# DCDC_int.net
KiCad netlist of a schematic drawn in Altium Designer
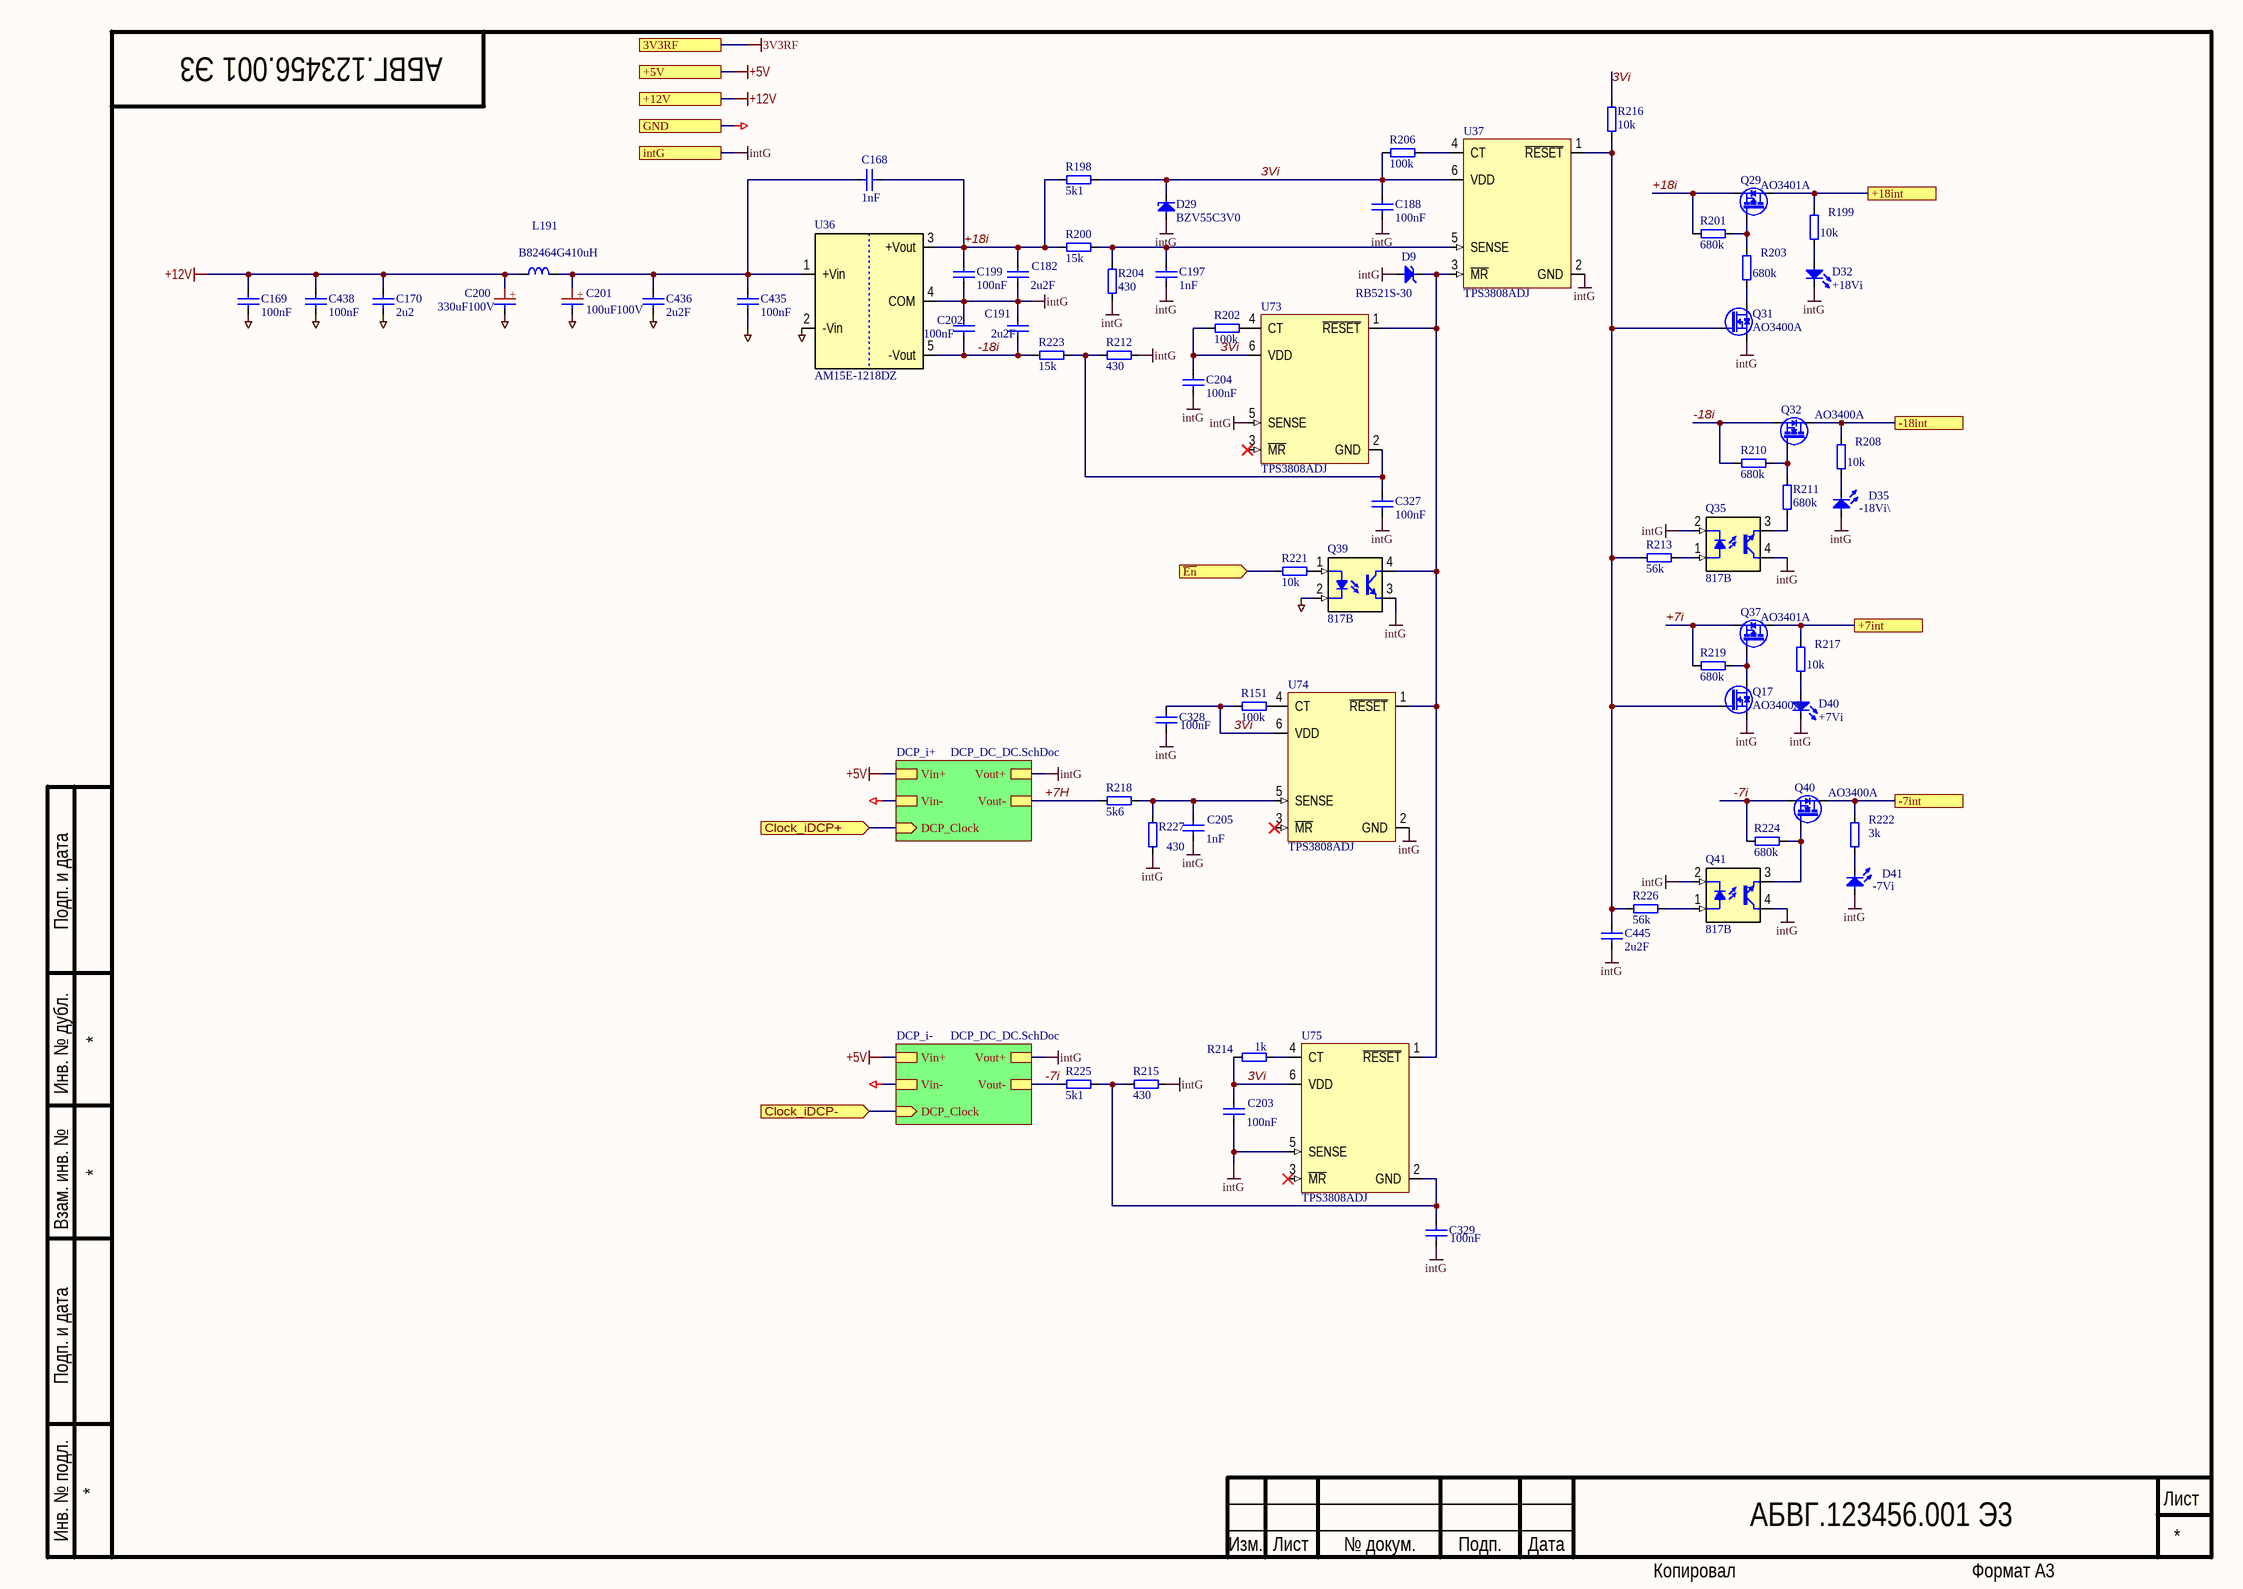
[diagram p0: DCDC_int.SchDoc]

(export (version "E")
  (design (tool "Eeschema 10.0.6"))
  (components
    (comp (ref "C168")
      (value "1nF")
      (footprint "SMD0805CAP")
      (description "Чип конденсатор 0805")
      (fields (field (name "VOLTAGE") "25V") (field (name "TOLERANCE") "20%"))
      (libsource (lib "DDSintLib") (part "C0805"))
    )
    (comp (ref "C169")
      (value "100nF")
      (footprint "SMD0805CAP")
      (description "Чип конденсатор 0805")
      (fields (field (name "VOLTAGE") "25V") (field (name "TOLERANCE") "20%"))
      (libsource (lib "DDSintLib") (part "C0805"))
    )
    (comp (ref "C170")
      (value "2u2")
      (footprint "SMD0805CAP")
      (description "Чип конденсатор 0805")
      (fields (field (name "VOLTAGE") "25V") (field (name "TOLERANCE") "20%"))
      (libsource (lib "DDSintLib") (part "C0805"))
    )
    (comp (ref "C182")
      (value "2u2F")
      (footprint "SMD0805CAP")
      (description "Чип конденсатор 0805")
      (fields (field (name "VOLTAGE") "25V") (field (name "TOLERANCE") "20%"))
      (libsource (lib "DDSintLib") (part "C0805"))
    )
    (comp (ref "C188")
      (value "100nF")
      (footprint "SMD0805CAP")
      (description "Чип конденсатор 0805")
      (fields (field (name "VOLTAGE") "25V") (field (name "TOLERANCE") "20%"))
      (libsource (lib "DDSintLib") (part "C0805"))
    )
    (comp (ref "C191")
      (value "2u2F")
      (footprint "SMD0805CAP")
      (description "Чип конденсатор 0805")
      (fields (field (name "VOLTAGE") "25V") (field (name "TOLERANCE") "20%"))
      (libsource (lib "DDSintLib") (part "C0805"))
    )
    (comp (ref "C197")
      (value "1nF")
      (footprint "SMD0805CAP")
      (description "Чип конденсатор 0805")
      (fields (field (name "VOLTAGE") "25V") (field (name "TOLERANCE") "20%"))
      (libsource (lib "DDSintLib") (part "C0805"))
    )
    (comp (ref "C199")
      (value "100nF")
      (footprint "SMD0805CAP")
      (description "Чип конденсатор 0805")
      (fields (field (name "VOLTAGE") "25V") (field (name "TOLERANCE") "20%"))
      (libsource (lib "DDSintLib") (part "C0805"))
    )
    (comp (ref "C200")
      (value "330uF100V")
      (footprint "CAPPR750-1600X2000")
      (description "Конденсатор полярный d16 p7.5мм")
      (fields (field (name "VOLTAGE") "100V") (field (name "TOLERANCE") "20%"))
      (libsource (lib "DDSintLib") (part "CAP_POL_7_5x16"))
    )
    (comp (ref "C201")
      (value "100uF100V")
      (footprint "CAPPR500-1000X1250")
      (description "Конденсатор полярный d10 p5мм")
      (fields (field (name "VOLTAGE") "100V") (field (name "TOLERANCE") "20%"))
      (libsource (lib "DDS1") (part "CAP_POL_5x10"))
    )
    (comp (ref "C202")
      (value "100nF")
      (footprint "SMD0805CAP")
      (description "Чип конденсатор 0805")
      (fields (field (name "VOLTAGE") "25V") (field (name "TOLERANCE") "20%"))
      (libsource (lib "DDSintLib") (part "C0805"))
    )
    (comp (ref "C203")
      (value "100nF")
      (footprint "SMD0805CAP")
      (description "Чип конденсатор 0805")
      (fields (field (name "VOLTAGE") "25V") (field (name "TOLERANCE") "20%"))
      (libsource (lib "DDSintLib") (part "C0805"))
    )
    (comp (ref "C204")
      (value "100nF")
      (footprint "SMD0805CAP")
      (description "Чип конденсатор 0805")
      (fields (field (name "VOLTAGE") "25V") (field (name "TOLERANCE") "20%"))
      (libsource (lib "DDSintLib") (part "C0805"))
    )
    (comp (ref "C205")
      (value "1nF")
      (footprint "SMD0805CAP")
      (description "Чип конденсатор 0805")
      (fields (field (name "VOLTAGE") "25V") (field (name "TOLERANCE") "20%"))
      (libsource (lib "DDSintLib") (part "C0805"))
    )
    (comp (ref "C327")
      (value "100nF")
      (footprint "SMD0805CAP")
      (description "Чип конденсатор 0805")
      (fields (field (name "VOLTAGE") "25V") (field (name "TOLERANCE") "20%"))
      (libsource (lib "DDSintLib") (part "C0805"))
    )
    (comp (ref "C328")
      (value "100nF")
      (footprint "SMD0805CAP")
      (description "Чип конденсатор 0805")
      (fields (field (name "VOLTAGE") "25V") (field (name "TOLERANCE") "20%"))
      (libsource (lib "DDSintLib") (part "C0805"))
    )
    (comp (ref "C329")
      (value "100nF")
      (footprint "SMD0805CAP")
      (description "Чип конденсатор 0805")
      (fields (field (name "VOLTAGE") "25V") (field (name "TOLERANCE") "20%"))
      (libsource (lib "DDSintLib") (part "C0805"))
    )
    (comp (ref "C435")
      (value "100nF")
      (footprint "SMD0805CAP")
      (description "Чип конденсатор 0805")
      (fields (field (name "VOLTAGE") "25V") (field (name "TOLERANCE") "20%"))
      (libsource (lib "DDSintLib") (part "C0805"))
    )
    (comp (ref "C436")
      (value "2u2F")
      (footprint "SMD0805CAP")
      (description "Чип конденсатор 0805")
      (fields (field (name "VOLTAGE") "25V") (field (name "TOLERANCE") "20%"))
      (libsource (lib "DDSintLib") (part "C0805"))
    )
    (comp (ref "C438")
      (value "100nF")
      (footprint "SMD0805CAP")
      (description "Чип конденсатор 0805")
      (fields (field (name "VOLTAGE") "25V") (field (name "TOLERANCE") "20%"))
      (libsource (lib "DDSintLib") (part "C0805"))
    )
    (comp (ref "C445")
      (value "2u2F")
      (footprint "SMD0805CAP")
      (description "Чип конденсатор 0805")
      (fields (field (name "VOLTAGE") "25V") (field (name "TOLERANCE") "20%"))
      (libsource (lib "DDSintLib") (part "C0805"))
    )
    (comp (ref "D9")
      (value "RB521S-30")
      (footprint "SODFL1608X65N")
      (description "Чип Шоттки диод")
      (fields (field (name "VOLTAGE") "30V"))
      (libsource (lib "DDSintLib") (part "RB521S-30"))
    )
    (comp (ref "D29")
      (value "BZV55C3V0")
      (footprint "DIOMELF3516N")
      (description "Чип cтабилитрон")
      (fields (field (name "VOLTAGE") "3V"))
      (libsource (lib "DDSintLib") (part "BZV55C"))
    )
    (comp (ref "D32")
      (value "+18Vi")
      (footprint "LED0603")
      (description "Чип светодиод 0603")
      (libsource (lib "DDSintLib") (part "LED0603"))
    )
    (comp (ref "D35")
      (value "-18V~{i}")
      (footprint "LED0603")
      (description "Чип светодиод 0603")
      (libsource (lib "DDSintLib") (part "LED0603"))
    )
    (comp (ref "D40")
      (value "+7Vi")
      (footprint "LED0603")
      (description "Чип светодиод 0603")
      (libsource (lib "DDSintLib") (part "LED0603"))
    )
    (comp (ref "D41")
      (value "-7Vi")
      (footprint "LED0603")
      (description "Чип светодиод 0603")
      (libsource (lib "DDSintLib") (part "LED0603"))
    )
    (comp (ref "L191")
      (value "B82464G410uH")
      (footprint "IND_COILCRAFT_MSS1038")
      (description "SMD Дроссель")
      (fields (field (name "VOLTAGE") "2") (field (name "TOLERANCE") "20%"))
      (libsource (lib "DDSintLib") (part "B82464G4"))
    )
    (comp (ref "Q17")
      (value "AO3400A")
      (footprint "SOT95P229X119-3N")
      (description "NMOS")
      (fields (field (name "VOLTAGE") "30V"))
      (libsource (lib "DDSintLib") (part "AO3400A"))
    )
    (comp (ref "Q29")
      (value "AO3401A")
      (footprint "SOT95P229X119-3N")
      (description "PMOS")
      (fields (field (name "VOLTAGE") "-30V"))
      (libsource (lib "DDSintLib") (part "AO3401A"))
    )
    (comp (ref "Q31")
      (value "AO3400A")
      (footprint "SOT95P229X119-3N")
      (description "NMOS")
      (fields (field (name "VOLTAGE") "30V"))
      (libsource (lib "DDSintLib") (part "AO3400A"))
    )
    (comp (ref "Q32")
      (value "AO3400A")
      (footprint "SOT95P229X119-3N")
      (description "NMOS")
      (fields (field (name "VOLTAGE") "30V"))
      (libsource (lib "DDSintLib") (part "AO3400A"))
    )
    (comp (ref "Q35")
      (value "817B")
      (footprint "DIP4-300")
      (description "Optotransistor")
      (fields (field (name "VOLTAGE") "35V"))
      (libsource (lib "") (part "817B_1"))
    )
    (comp (ref "Q37")
      (value "AO3401A")
      (footprint "SOT95P229X119-3N")
      (description "PMOS")
      (fields (field (name "VOLTAGE") "-30V"))
      (libsource (lib "DDSintLib") (part "AO3401A"))
    )
    (comp (ref "Q39")
      (value "817B")
      (footprint "DIP4-300")
      (description "Optotransistor")
      (fields (field (name "VOLTAGE") "35V"))
      (libsource (lib "DDS1") (part "817B"))
    )
    (comp (ref "Q40")
      (value "AO3400A")
      (footprint "SOT95P229X119-3N")
      (description "NMOS")
      (fields (field (name "VOLTAGE") "30V"))
      (libsource (lib "DDSintLib") (part "AO3400A"))
    )
    (comp (ref "Q41")
      (value "817B")
      (footprint "DIP4-300")
      (description "Optotransistor")
      (fields (field (name "VOLTAGE") "35V"))
      (libsource (lib "") (part "817B_1"))
    )
    (comp (ref "R151")
      (value "100k")
      (footprint "SMD0805RES")
      (description "Чип резистор 0805")
      (fields (field (name "TOLERANCE") "1%"))
      (libsource (lib "DDSintLib") (part "R0805"))
    )
    (comp (ref "R198")
      (value "5k1")
      (footprint "SMD0805RES")
      (description "Чип резистор 0805")
      (fields (field (name "TOLERANCE") "1%"))
      (libsource (lib "DDSintLib") (part "R0805"))
    )
    (comp (ref "R199")
      (value "10k")
      (footprint "SMD0805RES")
      (description "Чип резистор 0805")
      (fields (field (name "TOLERANCE") "1%"))
      (libsource (lib "DDSintLib") (part "R0805"))
    )
    (comp (ref "R200")
      (value "15k")
      (footprint "SMD0805RES")
      (description "Чип резистор 0805")
      (fields (field (name "TOLERANCE") "1%"))
      (libsource (lib "DDSintLib") (part "R0805"))
    )
    (comp (ref "R201")
      (value "680k")
      (footprint "SMD0805RES")
      (description "Чип резистор 0805")
      (fields (field (name "TOLERANCE") "1%"))
      (libsource (lib "DDSintLib") (part "R0805"))
    )
    (comp (ref "R202")
      (value "100k")
      (footprint "SMD0805RES")
      (description "Чип резистор 0805")
      (fields (field (name "TOLERANCE") "1%"))
      (libsource (lib "DDSintLib") (part "R0805"))
    )
    (comp (ref "R203")
      (value "680k")
      (footprint "SMD0805RES")
      (description "Чип резистор 0805")
      (fields (field (name "TOLERANCE") "1%"))
      (libsource (lib "DDSintLib") (part "R0805"))
    )
    (comp (ref "R204")
      (value "430")
      (footprint "SMD0805RES")
      (description "Чип резистор 0805")
      (fields (field (name "TOLERANCE") "1%"))
      (libsource (lib "DDSintLib") (part "R0805"))
    )
    (comp (ref "R206")
      (value "100k")
      (footprint "SMD0805RES")
      (description "Чип резистор 0805")
      (fields (field (name "TOLERANCE") "1%"))
      (libsource (lib "DDSintLib") (part "R0805"))
    )
    (comp (ref "R208")
      (value "10k")
      (footprint "SMD0805RES")
      (description "Чип резистор 0805")
      (fields (field (name "TOLERANCE") "1%"))
      (libsource (lib "DDSintLib") (part "R0805"))
    )
    (comp (ref "R210")
      (value "680k")
      (footprint "SMD0805RES")
      (description "Чип резистор 0805")
      (fields (field (name "TOLERANCE") "1%"))
      (libsource (lib "DDSintLib") (part "R0805"))
    )
    (comp (ref "R211")
      (value "680k")
      (footprint "SMD0805RES")
      (description "Чип резистор 0805")
      (fields (field (name "TOLERANCE") "1%"))
      (libsource (lib "DDSintLib") (part "R0805"))
    )
    (comp (ref "R212")
      (value "430")
      (footprint "SMD0805RES")
      (description "Чип резистор 0805")
      (fields (field (name "TOLERANCE") "1%"))
      (libsource (lib "DDSintLib") (part "R0805"))
    )
    (comp (ref "R213")
      (value "56k")
      (footprint "SMD0805RES")
      (description "Чип резистор 0805")
      (fields (field (name "TOLERANCE") "1%"))
      (libsource (lib "DDSintLib") (part "R0805"))
    )
    (comp (ref "R214")
      (value "1k")
      (footprint "SMD0805RES")
      (description "Чип резистор 0805")
      (fields (field (name "TOLERANCE") "1%"))
      (libsource (lib "DDSintLib") (part "R0805"))
    )
    (comp (ref "R215")
      (value "430")
      (footprint "SMD0805RES")
      (description "Чип резистор 0805")
      (fields (field (name "TOLERANCE") "1%"))
      (libsource (lib "DDSintLib") (part "R0805"))
    )
    (comp (ref "R216")
      (value "10k")
      (footprint "SMD0805RES")
      (description "Чип резистор 0805")
      (fields (field (name "TOLERANCE") "1%"))
      (libsource (lib "DDSintLib") (part "R0805"))
    )
    (comp (ref "R217")
      (value "10k")
      (footprint "SMD0805RES")
      (description "Чип резистор 0805")
      (fields (field (name "TOLERANCE") "1%"))
      (libsource (lib "DDSintLib") (part "R0805"))
    )
    (comp (ref "R218")
      (value "5k6")
      (footprint "SMD0805RES")
      (description "Чип резистор 0805")
      (fields (field (name "TOLERANCE") "1%"))
      (libsource (lib "DDSintLib") (part "R0805"))
    )
    (comp (ref "R219")
      (value "680k")
      (footprint "SMD0805RES")
      (description "Чип резистор 0805")
      (fields (field (name "TOLERANCE") "1%"))
      (libsource (lib "DDSintLib") (part "R0805"))
    )
    (comp (ref "R221")
      (value "10k")
      (footprint "SMD0805RES")
      (description "Чип резистор 0805")
      (fields (field (name "TOLERANCE") "1%"))
      (libsource (lib "DDSintLib") (part "R0805"))
    )
    (comp (ref "R222")
      (value "3k")
      (footprint "SMD0805RES")
      (description "Чип резистор 0805")
      (fields (field (name "TOLERANCE") "1%"))
      (libsource (lib "DDSintLib") (part "R0805"))
    )
    (comp (ref "R223")
      (value "15k")
      (footprint "SMD0805RES")
      (description "Чип резистор 0805")
      (fields (field (name "TOLERANCE") "1%"))
      (libsource (lib "DDSintLib") (part "R0805"))
    )
    (comp (ref "R224")
      (value "680k")
      (footprint "SMD0805RES")
      (description "Чип резистор 0805")
      (fields (field (name "TOLERANCE") "1%"))
      (libsource (lib "DDSintLib") (part "R0805"))
    )
    (comp (ref "R225")
      (value "5k1")
      (footprint "SMD0805RES")
      (description "Чип резистор 0805")
      (fields (field (name "TOLERANCE") "1%"))
      (libsource (lib "DDSintLib") (part "R0805"))
    )
    (comp (ref "R226")
      (value "56k")
      (footprint "SMD0805RES")
      (description "Чип резистор 0805")
      (fields (field (name "TOLERANCE") "1%"))
      (libsource (lib "DDSintLib") (part "R0805"))
    )
    (comp (ref "R227")
      (value "430")
      (footprint "SMD0805RES")
      (description "Чип резистор 0805")
      (fields (field (name "TOLERANCE") "1%"))
      (libsource (lib "DDSintLib") (part "R0805"))
    )
    (comp (ref "U36")
      (value "AM15E-1218DZ")
      (footprint "AM15E")
      (description "Negative LDO Linear stabilizer")
      (libsource (lib "DDS1") (part "AM15E-"))
    )
    (comp (ref "U37")
      (value "TPS3808ADJ")
      (footprint "SOT95P270X145-6N")
      (description "Supervisory Circuit. Low-Quiescent-Current, Programmable-Delay")
      (libsource (lib "DDS1") (part "TPS3808"))
    )
    (comp (ref "U73")
      (value "TPS3808ADJ")
      (footprint "SOT95P270X145-6N")
      (description "Supervisory Circuit. Low-Quiescent-Current, Programmable-Delay")
      (libsource (lib "DDS1") (part "TPS3808"))
    )
    (comp (ref "U74")
      (value "TPS3808ADJ")
      (footprint "SOT95P270X145-6N")
      (description "Supervisory Circuit. Low-Quiescent-Current, Programmable-Delay")
      (libsource (lib "DDS1") (part "TPS3808"))
    )
    (comp (ref "U75")
      (value "TPS3808ADJ")
      (footprint "SOT95P270X145-6N")
      (description "Supervisory Circuit. Low-Quiescent-Current, Programmable-Delay")
      (libsource (lib "DDS1") (part "TPS3808"))
    )
  )
  (nets
    (net (code "2") (name "+12V") (class "Default")
      (node (ref "C169") (pin "2") (pinfunction "2_2") (pintype "passive"))
      (node (ref "C170") (pin "2") (pinfunction "2_2") (pintype "passive"))
      (node (ref "C200") (pin "1") (pinfunction "+_1") (pintype "passive"))
      (node (ref "C438") (pin "2") (pinfunction "2_2") (pintype "passive"))
      (node (ref "L191") (pin "1") (pinfunction "1_1") (pintype "passive"))
    )
    (net (code "3") (name "/+7H") (class "Default")
      (node (ref "R218") (pin "2") (pinfunction "2_2") (pintype "passive"))
    )
    (net (code "4") (name "/+7i") (class "Default")
      (node (ref "Q37") (pin "2") (pinfunction "S_2") (pintype "passive"))
      (node (ref "R219") (pin "2") (pinfunction "2_2") (pintype "passive"))
    )
    (net (code "5") (name "/+7int") (class "Default")
      (node (ref "Q37") (pin "3") (pinfunction "D_3") (pintype "passive"))
      (node (ref "R217") (pin "2") (pinfunction "2_2") (pintype "passive"))
    )
    (net (code "6") (name "/+18i") (class "Default")
      (node (ref "C168") (pin "2") (pinfunction "2_2") (pintype "passive"))
      (node (ref "C182") (pin "2") (pinfunction "2_2") (pintype "passive"))
      (node (ref "C199") (pin "1") (pinfunction "1_1") (pintype "passive"))
      (node (ref "Q29") (pin "2") (pinfunction "S_2") (pintype "passive"))
      (node (ref "R198") (pin "2") (pinfunction "2_2") (pintype "passive"))
      (node (ref "R200") (pin "2") (pinfunction "2_2") (pintype "passive"))
      (node (ref "R201") (pin "2") (pinfunction "2_2") (pintype "passive"))
      (node (ref "U36") (pin "3") (pinfunction "+Vout_3") (pintype "power_in"))
    )
    (net (code "7") (name "/+18int") (class "Default")
      (node (ref "Q29") (pin "3") (pinfunction "D_3") (pintype "passive"))
      (node (ref "R199") (pin "2") (pinfunction "2_2") (pintype "passive"))
    )
    (net (code "8") (name "/-7i") (class "Default")
      (node (ref "Q40") (pin "2") (pinfunction "S_2") (pintype "passive"))
      (node (ref "R224") (pin "2") (pinfunction "2_2") (pintype "passive"))
      (node (ref "R225") (pin "2") (pinfunction "2_2") (pintype "passive"))
    )
    (net (code "9") (name "/-7int") (class "Default")
      (node (ref "Q40") (pin "3") (pinfunction "D_3") (pintype "passive"))
      (node (ref "R222") (pin "2") (pinfunction "2_2") (pintype "passive"))
    )
    (net (code "10") (name "/-18i") (class "Default")
      (node (ref "C191") (pin "1") (pinfunction "1_1") (pintype "passive"))
      (node (ref "C202") (pin "2") (pinfunction "2_2") (pintype "passive"))
      (node (ref "Q32") (pin "2") (pinfunction "S_2") (pintype "passive"))
      (node (ref "R210") (pin "2") (pinfunction "2_2") (pintype "passive"))
      (node (ref "R223") (pin "1") (pinfunction "1_1") (pintype "passive"))
      (node (ref "U36") (pin "5") (pinfunction "-Vout_5") (pintype "power_in"))
    )
    (net (code "11") (name "/-18int") (class "Default")
      (node (ref "Q32") (pin "3") (pinfunction "D_3") (pintype "passive"))
      (node (ref "R208") (pin "2") (pinfunction "2_2") (pintype "passive"))
    )
    (net (code "12") (name "/3Vi") (class "Default")
      (node (ref "C188") (pin "2") (pinfunction "2_2") (pintype "passive"))
      (node (ref "C203") (pin "2") (pinfunction "2_2") (pintype "passive"))
      (node (ref "C204") (pin "1") (pinfunction "1_1") (pintype "passive"))
      (node (ref "C328") (pin "2") (pinfunction "2_2") (pintype "passive"))
      (node (ref "D29") (pin "1") (pinfunction "C_1") (pintype "passive"))
      (node (ref "R151") (pin "1") (pinfunction "1_1") (pintype "passive"))
      (node (ref "R198") (pin "1") (pinfunction "1_1") (pintype "passive"))
      (node (ref "R202") (pin "1") (pinfunction "1_1") (pintype "passive"))
      (node (ref "R206") (pin "1") (pinfunction "1_1") (pintype "passive"))
      (node (ref "R214") (pin "1") (pinfunction "1_1") (pintype "passive"))
      (node (ref "R216") (pin "1") (pinfunction "1_1") (pintype "passive"))
      (node (ref "U37") (pin "6") (pinfunction "VDD_6") (pintype "power_in"))
      (node (ref "U73") (pin "6") (pinfunction "VDD_6") (pintype "power_in"))
      (node (ref "U74") (pin "6") (pinfunction "VDD_6") (pintype "power_in"))
      (node (ref "U75") (pin "6") (pinfunction "VDD_6") (pintype "power_in"))
    )
    (net (code "15") (name "/En") (class "Default")
      (node (ref "R221") (pin "1") (pinfunction "1_1") (pintype "passive"))
    )
    (net (code "17") (name "GND") (class "Default")
      (node (ref "C169") (pin "1") (pinfunction "1_1") (pintype "passive"))
      (node (ref "C170") (pin "1") (pinfunction "1_1") (pintype "passive"))
      (node (ref "C200") (pin "2") (pinfunction "2_2") (pintype "passive"))
      (node (ref "C201") (pin "2") (pinfunction "2_2") (pintype "passive"))
      (node (ref "C435") (pin "1") (pinfunction "1_1") (pintype "passive"))
      (node (ref "C436") (pin "1") (pinfunction "1_1") (pintype "passive"))
      (node (ref "C438") (pin "1") (pinfunction "1_1") (pintype "passive"))
      (node (ref "Q39") (pin "2") (pinfunction "C_2") (pintype "input"))
      (node (ref "U36") (pin "2") (pinfunction "-Vin_2") (pintype "power_in"))
    )
    (net (code "18") (name "Net-(C201-+)") (class "Default")
      (node (ref "C168") (pin "1") (pinfunction "1_1") (pintype "passive"))
      (node (ref "C201") (pin "1") (pinfunction "+_1") (pintype "passive"))
      (node (ref "C435") (pin "2") (pinfunction "2_2") (pintype "passive"))
      (node (ref "C436") (pin "2") (pinfunction "2_2") (pintype "passive"))
      (node (ref "L191") (pin "2") (pinfunction "2_2") (pintype "passive"))
      (node (ref "U36") (pin "1") (pinfunction "+Vin_1") (pintype "power_in"))
    )
    (net (code "19") (name "Net-(D9-C)") (class "Default")
      (node (ref "D9") (pin "1") (pinfunction "C_1") (pintype "passive"))
      (node (ref "Q39") (pin "4") (pinfunction "C_4") (pintype "open_collector"))
      (node (ref "U37") (pin "3") (pinfunction "~{MR}_3") (pintype "input"))
      (node (ref "U73") (pin "1") (pinfunction "~{RESET}_1") (pintype "open_collector"))
      (node (ref "U74") (pin "1") (pinfunction "~{RESET}_1") (pintype "open_collector"))
      (node (ref "U75") (pin "1") (pinfunction "~{RESET}_1") (pintype "open_collector"))
    )
    (net (code "20") (name "Net-(D32-A)") (class "Default")
      (node (ref "D32") (pin "2") (pinfunction "A_2") (pintype "passive"))
      (node (ref "R199") (pin "1") (pinfunction "1_1") (pintype "passive"))
    )
    (net (code "21") (name "Net-(D35-C)") (class "Default")
      (node (ref "D35") (pin "1") (pinfunction "C_1") (pintype "passive"))
      (node (ref "R208") (pin "1") (pinfunction "1_1") (pintype "passive"))
    )
    (net (code "22") (name "Net-(D40-A)") (class "Default")
      (node (ref "D40") (pin "2") (pinfunction "A_2") (pintype "passive"))
      (node (ref "R217") (pin "1") (pinfunction "1_1") (pintype "passive"))
    )
    (net (code "23") (name "Net-(D41-C)") (class "Default")
      (node (ref "D41") (pin "1") (pinfunction "C_1") (pintype "passive"))
      (node (ref "R222") (pin "1") (pinfunction "1_1") (pintype "passive"))
    )
    (net (code "24") (name "Net-(Q17-D)") (class "Default")
      (node (ref "Q17") (pin "3") (pinfunction "D_3") (pintype "passive"))
      (node (ref "Q37") (pin "1") (pinfunction "G_1") (pintype "passive"))
      (node (ref "R219") (pin "1") (pinfunction "1_1") (pintype "passive"))
    )
    (net (code "25") (name "Net-(Q17-G)") (class "Default")
      (node (ref "C445") (pin "1") (pinfunction "1_1") (pintype "passive"))
      (node (ref "Q17") (pin "1") (pinfunction "G_1") (pintype "passive"))
      (node (ref "Q31") (pin "1") (pinfunction "G_1") (pintype "passive"))
      (node (ref "R213") (pin "1") (pinfunction "1_1") (pintype "passive"))
      (node (ref "R216") (pin "2") (pinfunction "2_2") (pintype "passive"))
      (node (ref "R226") (pin "1") (pinfunction "1_1") (pintype "passive"))
      (node (ref "U37") (pin "1") (pinfunction "~{RESET}_1") (pintype "open_collector"))
    )
    (net (code "26") (name "Net-(Q29-G)") (class "Default")
      (node (ref "Q29") (pin "1") (pinfunction "G_1") (pintype "passive"))
      (node (ref "R201") (pin "1") (pinfunction "1_1") (pintype "passive"))
      (node (ref "R203") (pin "2") (pinfunction "2_2") (pintype "passive"))
    )
    (net (code "27") (name "Net-(Q31-D)") (class "Default")
      (node (ref "Q31") (pin "3") (pinfunction "D_3") (pintype "passive"))
      (node (ref "R203") (pin "1") (pinfunction "1_1") (pintype "passive"))
    )
    (net (code "28") (name "Net-(Q32-G)") (class "Default")
      (node (ref "Q32") (pin "1") (pinfunction "G_1") (pintype "passive"))
      (node (ref "R210") (pin "1") (pinfunction "1_1") (pintype "passive"))
      (node (ref "R211") (pin "2") (pinfunction "2_2") (pintype "passive"))
    )
    (net (code "29") (name "Net-(Q35-A)") (class "Default")
      (node (ref "Q35") (pin "1") (pinfunction "A_1") (pintype "input"))
      (node (ref "R213") (pin "2") (pinfunction "2_2") (pintype "passive"))
    )
    (net (code "30") (name "Net-(Q35-E)") (class "Default")
      (node (ref "Q35") (pin "3") (pinfunction "E_3") (pintype "open_emitter"))
      (node (ref "R211") (pin "1") (pinfunction "1_1") (pintype "passive"))
    )
    (net (code "31") (name "Net-(Q39-A)") (class "Default")
      (node (ref "Q39") (pin "1") (pinfunction "A_1") (pintype "input"))
      (node (ref "R221") (pin "2") (pinfunction "2_2") (pintype "passive"))
    )
    (net (code "32") (name "Net-(Q40-G)") (class "Default")
      (node (ref "Q40") (pin "1") (pinfunction "G_1") (pintype "passive"))
      (node (ref "Q41") (pin "3") (pinfunction "E_3") (pintype "open_emitter"))
      (node (ref "R224") (pin "1") (pinfunction "1_1") (pintype "passive"))
    )
    (net (code "33") (name "Net-(Q41-A)") (class "Default")
      (node (ref "Q41") (pin "1") (pinfunction "A_1") (pintype "input"))
      (node (ref "R226") (pin "2") (pinfunction "2_2") (pintype "passive"))
    )
    (net (code "34") (name "Net-(U37-CT)") (class "Default")
      (node (ref "R206") (pin "2") (pinfunction "2_2") (pintype "passive"))
      (node (ref "U37") (pin "4") (pinfunction "CT_4") (pintype "passive"))
    )
    (net (code "35") (name "Net-(U37-SENSE)") (class "Default")
      (node (ref "C197") (pin "2") (pinfunction "2_2") (pintype "passive"))
      (node (ref "R200") (pin "1") (pinfunction "1_1") (pintype "passive"))
      (node (ref "R204") (pin "1") (pinfunction "1_1") (pintype "passive"))
      (node (ref "U37") (pin "5") (pinfunction "SENSE_5") (pintype "input"))
    )
    (net (code "36") (name "Net-(U73-CT)") (class "Default")
      (node (ref "R202") (pin "2") (pinfunction "2_2") (pintype "passive"))
      (node (ref "U73") (pin "4") (pinfunction "CT_4") (pintype "passive"))
    )
    (net (code "37") (name "Net-(U73-GND)") (class "Default")
      (node (ref "C327") (pin "1") (pinfunction "1_1") (pintype "passive"))
      (node (ref "R212") (pin "1") (pinfunction "1_1") (pintype "passive"))
      (node (ref "R223") (pin "2") (pinfunction "2_2") (pintype "passive"))
      (node (ref "U73") (pin "2") (pinfunction "GND_2") (pintype "power_in"))
    )
    (net (code "38") (name "Net-(U74-CT)") (class "Default")
      (node (ref "R151") (pin "2") (pinfunction "2_2") (pintype "passive"))
      (node (ref "U74") (pin "4") (pinfunction "CT_4") (pintype "passive"))
    )
    (net (code "39") (name "Net-(U74-SENSE)") (class "Default")
      (node (ref "C205") (pin "2") (pinfunction "2_2") (pintype "passive"))
      (node (ref "R218") (pin "1") (pinfunction "1_1") (pintype "passive"))
      (node (ref "R227") (pin "1") (pinfunction "1_1") (pintype "passive"))
      (node (ref "U74") (pin "5") (pinfunction "SENSE_5") (pintype "input"))
    )
    (net (code "40") (name "Net-(U75-CT)") (class "Default")
      (node (ref "R214") (pin "2") (pinfunction "2_2") (pintype "passive"))
      (node (ref "U75") (pin "4") (pinfunction "CT_4") (pintype "passive"))
    )
    (net (code "41") (name "Net-(U75-GND)") (class "Default")
      (node (ref "C329") (pin "2") (pinfunction "2_2") (pintype "passive"))
      (node (ref "R215") (pin "1") (pinfunction "1_1") (pintype "passive"))
      (node (ref "R225") (pin "1") (pinfunction "1_1") (pintype "passive"))
      (node (ref "U75") (pin "2") (pinfunction "GND_2") (pintype "power_in"))
    )
    (net (code "42") (name "intG") (class "Default")
      (node (ref "C182") (pin "1") (pinfunction "1_1") (pintype "passive"))
      (node (ref "C188") (pin "1") (pinfunction "1_1") (pintype "passive"))
      (node (ref "C191") (pin "2") (pinfunction "2_2") (pintype "passive"))
      (node (ref "C197") (pin "1") (pinfunction "1_1") (pintype "passive"))
      (node (ref "C199") (pin "2") (pinfunction "2_2") (pintype "passive"))
      (node (ref "C202") (pin "1") (pinfunction "1_1") (pintype "passive"))
      (node (ref "C203") (pin "1") (pinfunction "1_1") (pintype "passive"))
      (node (ref "C204") (pin "2") (pinfunction "2_2") (pintype "passive"))
      (node (ref "C205") (pin "1") (pinfunction "1_1") (pintype "passive"))
      (node (ref "C327") (pin "2") (pinfunction "2_2") (pintype "passive"))
      (node (ref "C328") (pin "1") (pinfunction "1_1") (pintype "passive"))
      (node (ref "C329") (pin "1") (pinfunction "1_1") (pintype "passive"))
      (node (ref "C445") (pin "2") (pinfunction "2_2") (pintype "passive"))
      (node (ref "D29") (pin "2") (pinfunction "A_2") (pintype "passive"))
      (node (ref "D32") (pin "1") (pinfunction "C_1") (pintype "passive"))
      (node (ref "D35") (pin "2") (pinfunction "A_2") (pintype "passive"))
      (node (ref "D40") (pin "1") (pinfunction "C_1") (pintype "passive"))
      (node (ref "D41") (pin "2") (pinfunction "A_2") (pintype "passive"))
      (node (ref "D9") (pin "2") (pinfunction "A_2") (pintype "passive"))
      (node (ref "Q17") (pin "2") (pinfunction "S_2") (pintype "passive"))
      (node (ref "Q31") (pin "2") (pinfunction "S_2") (pintype "passive"))
      (node (ref "Q35") (pin "2") (pinfunction "C_2") (pintype "input"))
      (node (ref "Q35") (pin "4") (pinfunction "C_4") (pintype "open_collector"))
      (node (ref "Q39") (pin "3") (pinfunction "E_3") (pintype "open_emitter"))
      (node (ref "Q41") (pin "2") (pinfunction "C_2") (pintype "input"))
      (node (ref "Q41") (pin "4") (pinfunction "C_4") (pintype "open_collector"))
      (node (ref "R204") (pin "2") (pinfunction "2_2") (pintype "passive"))
      (node (ref "R212") (pin "2") (pinfunction "2_2") (pintype "passive"))
      (node (ref "R215") (pin "2") (pinfunction "2_2") (pintype "passive"))
      (node (ref "R227") (pin "2") (pinfunction "2_2") (pintype "passive"))
      (node (ref "U36") (pin "4") (pinfunction "COM_4") (pintype "power_in"))
      (node (ref "U37") (pin "2") (pinfunction "GND_2") (pintype "power_in"))
      (node (ref "U73") (pin "5") (pinfunction "SENSE_5") (pintype "input"))
      (node (ref "U74") (pin "2") (pinfunction "GND_2") (pintype "power_in"))
      (node (ref "U75") (pin "5") (pinfunction "SENSE_5") (pintype "input"))
    )
    (net (code "43") (name "unconnected-(U73-~{MR}-Pad3)") (class "Default")
      (node (ref "U73") (pin "3") (pinfunction "~{MR}_3") (pintype "input+no_connect"))
    )
    (net (code "44") (name "unconnected-(U74-~{MR}-Pad3)") (class "Default")
      (node (ref "U74") (pin "3") (pinfunction "~{MR}_3") (pintype "input+no_connect"))
    )
    (net (code "45") (name "unconnected-(U75-~{MR}-Pad3)") (class "Default")
      (node (ref "U75") (pin "3") (pinfunction "~{MR}_3") (pintype "input+no_connect"))
    )
  )
)
